# 6_cpu_registers_a.net
KiCad netlist of a schematic drawn in EAGLE
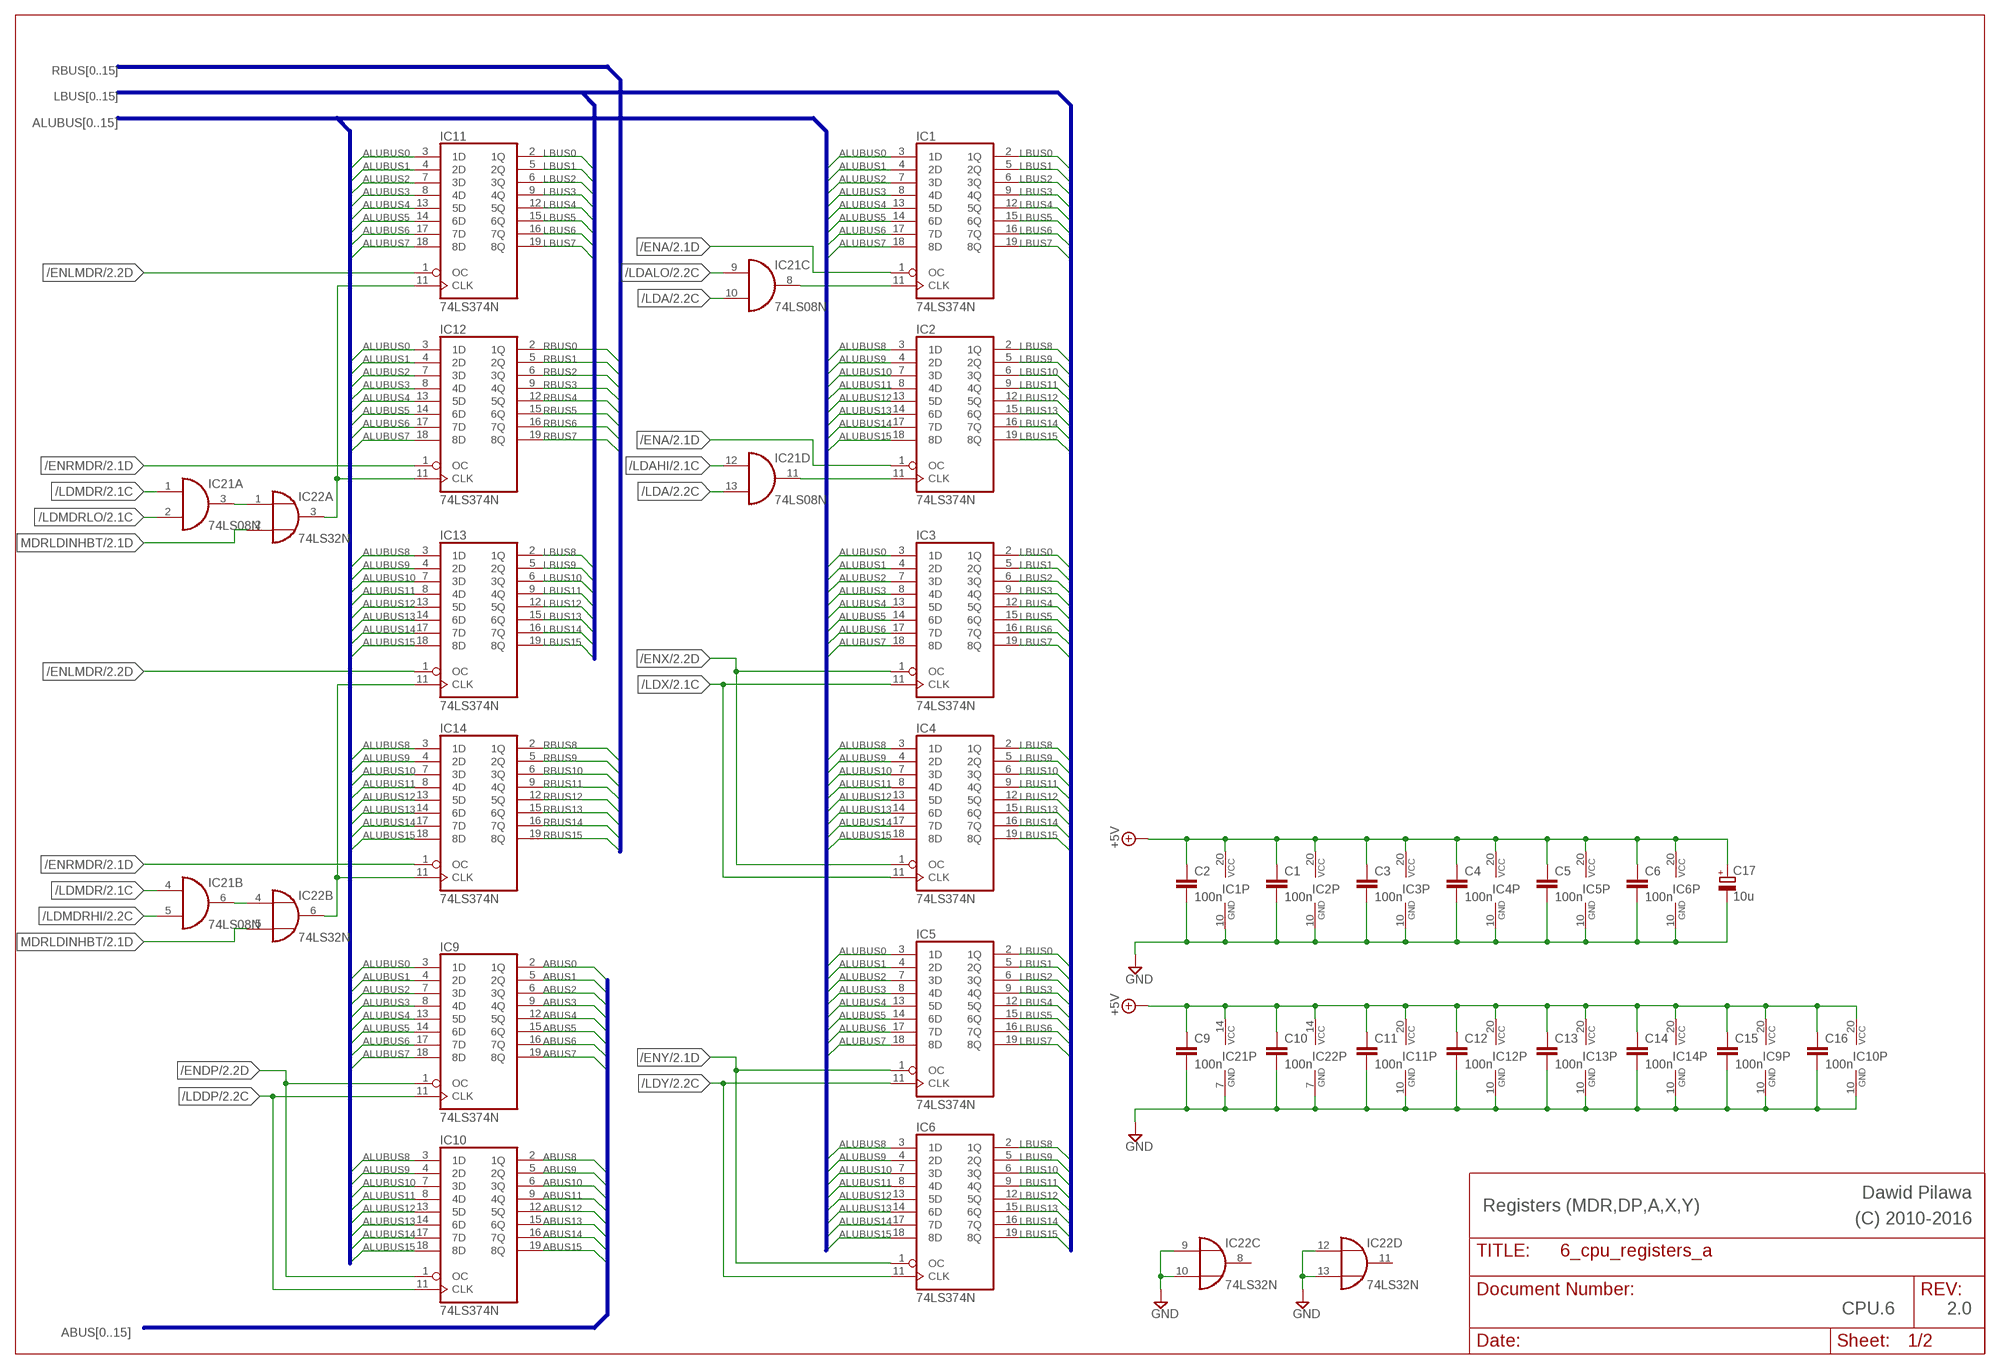
[diagram p0: schematic, sheet 1]
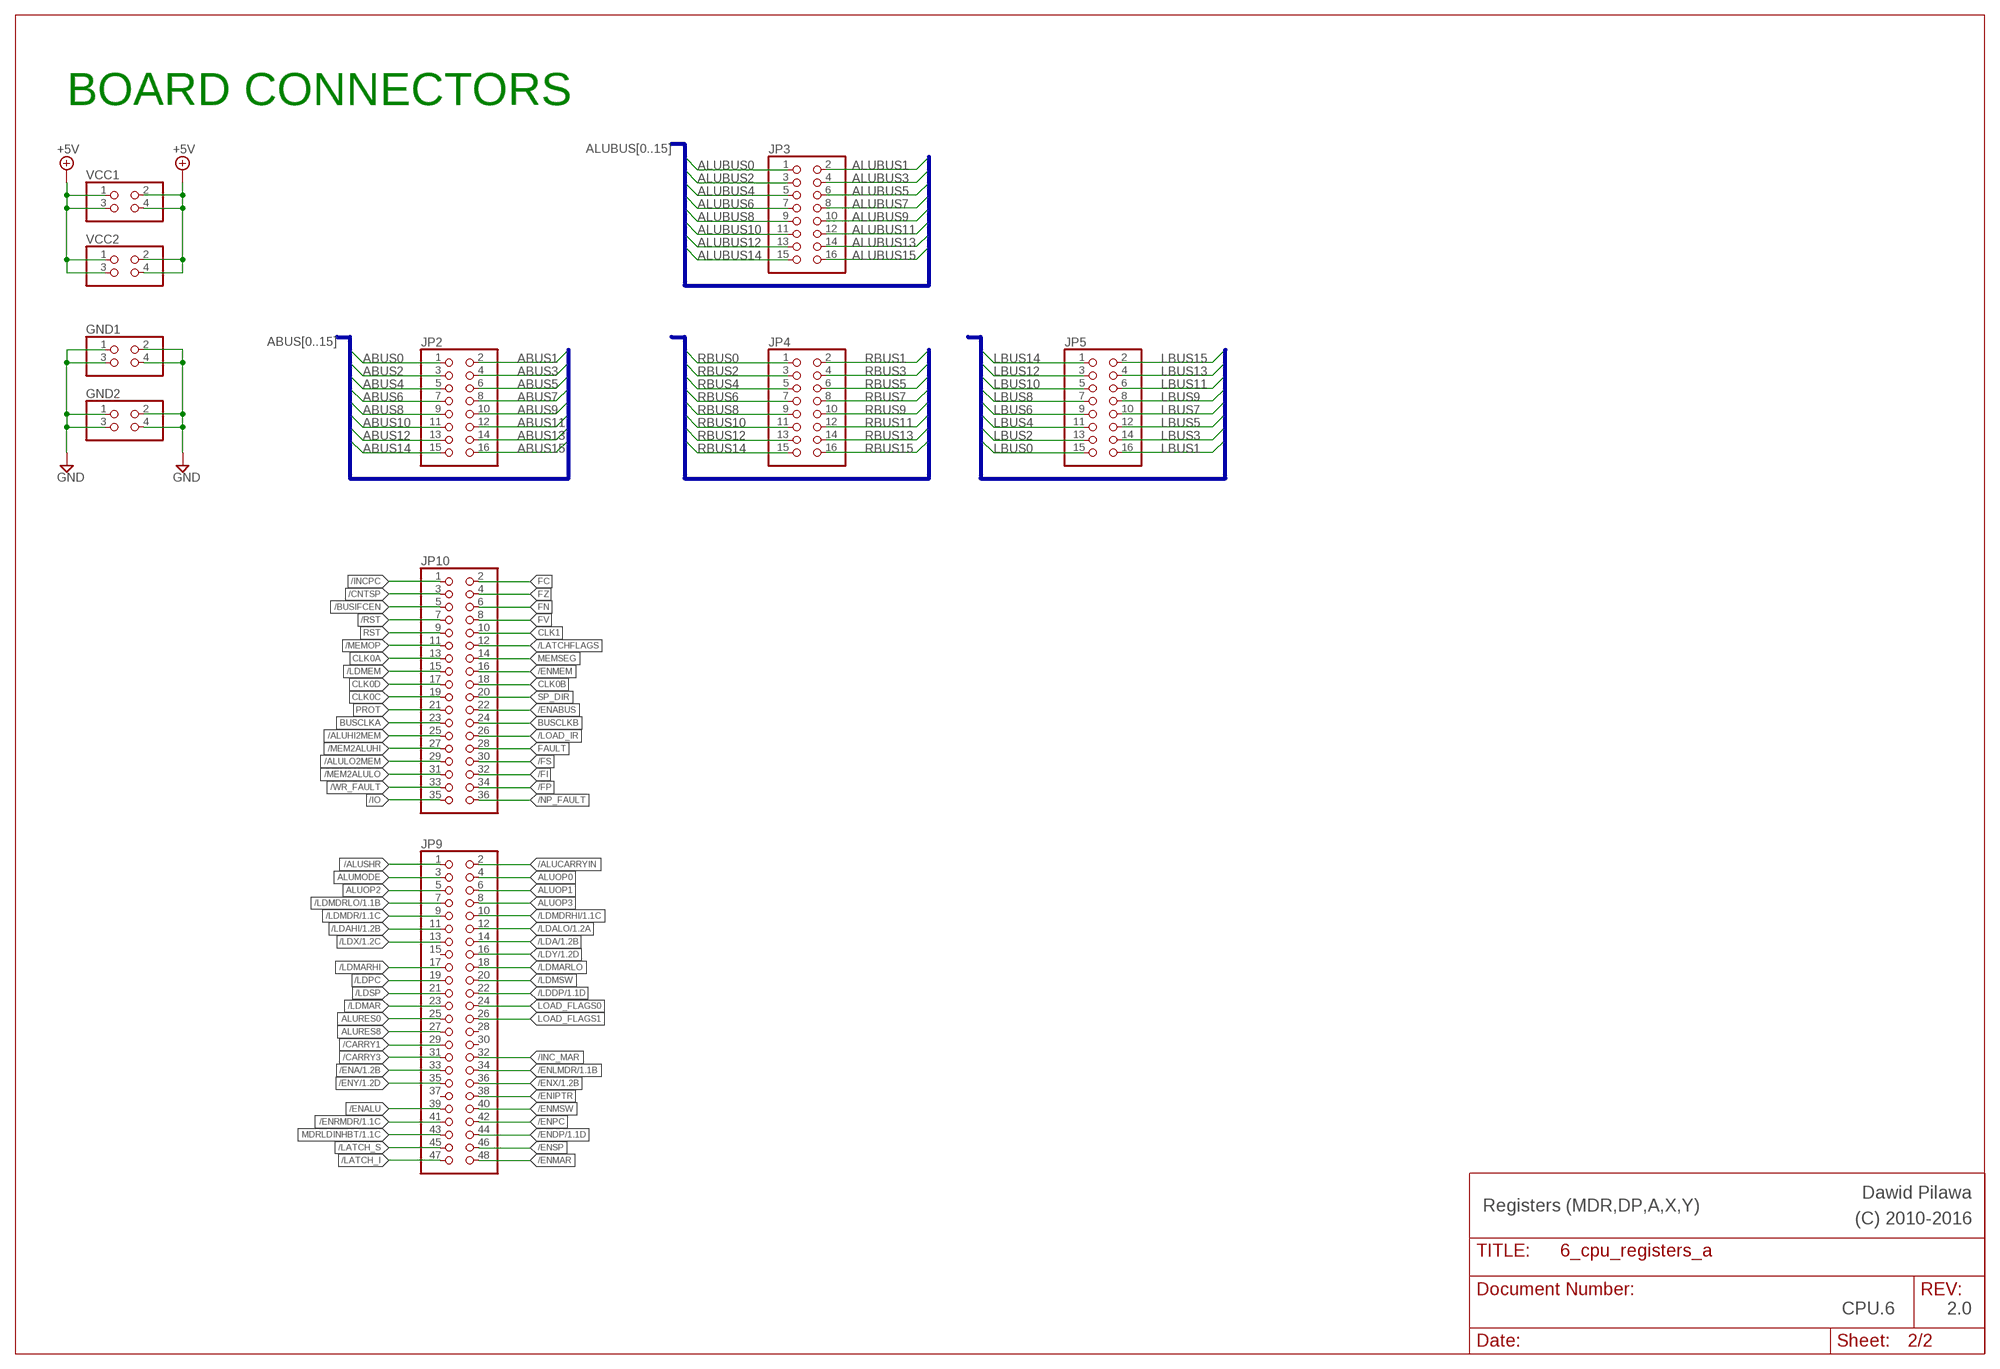
[diagram p1: schematic, sheet 2]

(export (version "E")
  (design (tool "Eeschema 10.0.6"))
  (components
    (comp (ref "C1")
      (value "100n")
      (footprint "eagle-import:C050-024X044")
      (libsource (lib "eagle-import") (part "C-EU050-024X044"))
    )
    (comp (ref "C2")
      (value "100n")
      (footprint "eagle-import:C050-024X044")
      (libsource (lib "eagle-import") (part "C-EU050-024X044"))
    )
    (comp (ref "C3")
      (value "100n")
      (footprint "eagle-import:C050-024X044")
      (libsource (lib "eagle-import") (part "C-EU050-024X044"))
    )
    (comp (ref "C4")
      (value "100n")
      (footprint "eagle-import:C050-024X044")
      (libsource (lib "eagle-import") (part "C-EU050-024X044"))
    )
    (comp (ref "C5")
      (value "100n")
      (footprint "eagle-import:C050-024X044")
      (libsource (lib "eagle-import") (part "C-EU050-024X044"))
    )
    (comp (ref "C6")
      (value "100n")
      (footprint "eagle-import:C050-024X044")
      (libsource (lib "eagle-import") (part "C-EU050-024X044"))
    )
    (comp (ref "C9")
      (value "100n")
      (footprint "eagle-import:C050-024X044")
      (libsource (lib "eagle-import") (part "C-EU050-024X044"))
    )
    (comp (ref "C10")
      (value "100n")
      (footprint "eagle-import:C050-024X044")
      (libsource (lib "eagle-import") (part "C-EU050-024X044"))
    )
    (comp (ref "C11")
      (value "100n")
      (footprint "eagle-import:C050-024X044")
      (libsource (lib "eagle-import") (part "C-EU050-024X044"))
    )
    (comp (ref "C12")
      (value "100n")
      (footprint "eagle-import:C050-024X044")
      (libsource (lib "eagle-import") (part "C-EU050-024X044"))
    )
    (comp (ref "C13")
      (value "100n")
      (footprint "eagle-import:C050-024X044")
      (libsource (lib "eagle-import") (part "C-EU050-024X044"))
    )
    (comp (ref "C14")
      (value "100n")
      (footprint "eagle-import:C050-024X044")
      (libsource (lib "eagle-import") (part "C-EU050-024X044"))
    )
    (comp (ref "C15")
      (value "100n")
      (footprint "eagle-import:C050-024X044")
      (libsource (lib "eagle-import") (part "C-EU050-024X044"))
    )
    (comp (ref "C16")
      (value "100n")
      (footprint "eagle-import:C050-024X044")
      (libsource (lib "eagle-import") (part "C-EU050-024X044"))
    )
    (comp (ref "C17")
      (value "10u")
      (footprint "eagle-import:E2,5-6")
      (libsource (lib "eagle-import") (part "CPOL-EUE2.5-6"))
    )
    (comp (ref "IC1")
      (value "74LS374N")
      (footprint "eagle-import:DIL20")
      (libsource (lib "eagle-import") (part "74374NLS"))
    )
    (comp (ref "IC2")
      (value "74LS374N")
      (footprint "eagle-import:DIL20")
      (libsource (lib "eagle-import") (part "74374NLS"))
    )
    (comp (ref "IC3")
      (value "74LS374N")
      (footprint "eagle-import:DIL20")
      (libsource (lib "eagle-import") (part "74374NLS"))
    )
    (comp (ref "IC4")
      (value "74LS374N")
      (footprint "eagle-import:DIL20")
      (libsource (lib "eagle-import") (part "74374NLS"))
    )
    (comp (ref "IC5")
      (value "74LS374N")
      (footprint "eagle-import:DIL20")
      (libsource (lib "eagle-import") (part "74374NLS"))
    )
    (comp (ref "IC6")
      (value "74LS374N")
      (footprint "eagle-import:DIL20")
      (libsource (lib "eagle-import") (part "74374NLS"))
    )
    (comp (ref "IC9")
      (value "74LS374N")
      (footprint "eagle-import:DIL20")
      (libsource (lib "eagle-import") (part "74374NLS"))
    )
    (comp (ref "IC10")
      (value "74LS374N")
      (footprint "eagle-import:DIL20")
      (libsource (lib "eagle-import") (part "74374NLS"))
    )
    (comp (ref "IC11")
      (value "74LS374N")
      (footprint "eagle-import:DIL20")
      (libsource (lib "eagle-import") (part "74374NLS"))
    )
    (comp (ref "IC12")
      (value "74LS374N")
      (footprint "eagle-import:DIL20")
      (libsource (lib "eagle-import") (part "74374NLS"))
    )
    (comp (ref "IC13")
      (value "74LS374N")
      (footprint "eagle-import:DIL20")
      (libsource (lib "eagle-import") (part "74374NLS"))
    )
    (comp (ref "IC14")
      (value "74LS374N")
      (footprint "eagle-import:DIL20")
      (libsource (lib "eagle-import") (part "74374NLS"))
    )
    (comp (ref "IC21")
      (value "74LS08N")
      (footprint "eagle-import:DIL14")
      (libsource (lib "eagle-import") (part "7408NLS"))
    )
    (comp (ref "IC22")
      (value "74LS32N")
      (footprint "eagle-import:DIL14")
      (libsource (lib "eagle-import") (part "7432NLS"))
    )
    (comp (ref "GND1")
      (value "PINHD-2X2")
      (footprint "eagle-import:2X02")
      (libsource (lib "eagle-import") (part "PINHD-2X2"))
    )
    (comp (ref "GND2")
      (value "PINHD-2X2")
      (footprint "eagle-import:2X02")
      (libsource (lib "eagle-import") (part "PINHD-2X2"))
    )
    (comp (ref "JP2")
      (value "PINHD-2X8")
      (footprint "eagle-import:2X08")
      (libsource (lib "eagle-import") (part "PINHD-2X8"))
    )
    (comp (ref "JP3")
      (value "PINHD-2X8")
      (footprint "eagle-import:2X08")
      (libsource (lib "eagle-import") (part "PINHD-2X8"))
    )
    (comp (ref "JP4")
      (value "PINHD-2X8")
      (footprint "eagle-import:2X08")
      (libsource (lib "eagle-import") (part "PINHD-2X8"))
    )
    (comp (ref "JP5")
      (value "PINHD-2X8")
      (footprint "eagle-import:2X08")
      (libsource (lib "eagle-import") (part "PINHD-2X8"))
    )
    (comp (ref "JP9")
      (value "PINHD-2X24")
      (footprint "eagle-import:2X24")
      (libsource (lib "eagle-import") (part "PINHD-2X24"))
    )
    (comp (ref "JP10")
      (value "PINHD-2X18")
      (footprint "eagle-import:2X18")
      (libsource (lib "eagle-import") (part "PINHD-2X18"))
    )
    (comp (ref "VCC1")
      (value "PINHD-2X2")
      (footprint "eagle-import:2X02")
      (libsource (lib "eagle-import") (part "PINHD-2X2"))
    )
    (comp (ref "VCC2")
      (value "PINHD-2X2")
      (footprint "eagle-import:2X02")
      (libsource (lib "eagle-import") (part "PINHD-2X2"))
    )
  )
  (nets
    (net (code "1") (name "+5V") (class "Default")
      (node (ref "C1") (pin "1") (pinfunction "1_1") (pintype "passive"))
      (node (ref "C10") (pin "1") (pinfunction "1_1") (pintype "passive"))
      (node (ref "C11") (pin "1") (pinfunction "1_1") (pintype "passive"))
      (node (ref "C12") (pin "1") (pinfunction "1_1") (pintype "passive"))
      (node (ref "C13") (pin "1") (pinfunction "1_1") (pintype "passive"))
      (node (ref "C14") (pin "1") (pinfunction "1_1") (pintype "passive"))
      (node (ref "C15") (pin "1") (pinfunction "1_1") (pintype "passive"))
      (node (ref "C16") (pin "1") (pinfunction "1_1") (pintype "passive"))
      (node (ref "C17") (pin "+") (pinfunction "+_+") (pintype "passive"))
      (node (ref "C2") (pin "1") (pinfunction "1_1") (pintype "passive"))
      (node (ref "C3") (pin "1") (pinfunction "1_1") (pintype "passive"))
      (node (ref "C4") (pin "1") (pinfunction "1_1") (pintype "passive"))
      (node (ref "C5") (pin "1") (pinfunction "1_1") (pintype "passive"))
      (node (ref "C6") (pin "1") (pinfunction "1_1") (pintype "passive"))
      (node (ref "C9") (pin "1") (pinfunction "1_1") (pintype "passive"))
      (node (ref "IC1") (pin "20") (pinfunction "VCC_20") (pintype "power_in"))
      (node (ref "IC10") (pin "20") (pinfunction "VCC_20") (pintype "power_in"))
      (node (ref "IC11") (pin "20") (pinfunction "VCC_20") (pintype "power_in"))
      (node (ref "IC12") (pin "20") (pinfunction "VCC_20") (pintype "power_in"))
      (node (ref "IC13") (pin "20") (pinfunction "VCC_20") (pintype "power_in"))
      (node (ref "IC14") (pin "20") (pinfunction "VCC_20") (pintype "power_in"))
      (node (ref "IC2") (pin "20") (pinfunction "VCC_20") (pintype "power_in"))
      (node (ref "IC21") (pin "14") (pinfunction "VCC_14") (pintype "power_in"))
      (node (ref "IC22") (pin "14") (pinfunction "VCC_14") (pintype "power_in"))
      (node (ref "IC3") (pin "20") (pinfunction "VCC_20") (pintype "power_in"))
      (node (ref "IC4") (pin "20") (pinfunction "VCC_20") (pintype "power_in"))
      (node (ref "IC5") (pin "20") (pinfunction "VCC_20") (pintype "power_in"))
      (node (ref "IC6") (pin "20") (pinfunction "VCC_20") (pintype "power_in"))
      (node (ref "IC9") (pin "20") (pinfunction "VCC_20") (pintype "power_in"))
      (node (ref "VCC1") (pin "1") (pinfunction "1_1") (pintype "passive"))
      (node (ref "VCC1") (pin "2") (pinfunction "2_2") (pintype "passive"))
      (node (ref "VCC1") (pin "3") (pinfunction "3_3") (pintype "passive"))
      (node (ref "VCC1") (pin "4") (pinfunction "4_4") (pintype "passive"))
      (node (ref "VCC2") (pin "1") (pinfunction "1_1") (pintype "passive"))
      (node (ref "VCC2") (pin "2") (pinfunction "2_2") (pintype "passive"))
      (node (ref "VCC2") (pin "3") (pinfunction "3_3") (pintype "passive"))
      (node (ref "VCC2") (pin "4") (pinfunction "4_4") (pintype "passive"))
    )
    (net (code "8") (name "ABUS0") (class "Default")
      (node (ref "IC9") (pin "2") (pinfunction "1Q_2") (pintype "tri_state"))
      (node (ref "JP2") (pin "1") (pinfunction "1_1") (pintype "passive"))
    )
    (net (code "9") (name "ABUS1") (class "Default")
      (node (ref "IC9") (pin "5") (pinfunction "2Q_5") (pintype "tri_state"))
      (node (ref "JP2") (pin "2") (pinfunction "2_2") (pintype "passive"))
    )
    (net (code "10") (name "ABUS2") (class "Default")
      (node (ref "IC9") (pin "6") (pinfunction "3Q_6") (pintype "tri_state"))
      (node (ref "JP2") (pin "3") (pinfunction "3_3") (pintype "passive"))
    )
    (net (code "11") (name "ABUS3") (class "Default")
      (node (ref "IC9") (pin "9") (pinfunction "4Q_9") (pintype "tri_state"))
      (node (ref "JP2") (pin "4") (pinfunction "4_4") (pintype "passive"))
    )
    (net (code "12") (name "ABUS4") (class "Default")
      (node (ref "IC9") (pin "12") (pinfunction "5Q_12") (pintype "tri_state"))
      (node (ref "JP2") (pin "5") (pinfunction "5_5") (pintype "passive"))
    )
    (net (code "13") (name "ABUS5") (class "Default")
      (node (ref "IC9") (pin "15") (pinfunction "6Q_15") (pintype "tri_state"))
      (node (ref "JP2") (pin "6") (pinfunction "6_6") (pintype "passive"))
    )
    (net (code "14") (name "ABUS6") (class "Default")
      (node (ref "IC9") (pin "16") (pinfunction "7Q_16") (pintype "tri_state"))
      (node (ref "JP2") (pin "7") (pinfunction "7_7") (pintype "passive"))
    )
    (net (code "15") (name "ABUS7") (class "Default")
      (node (ref "IC9") (pin "19") (pinfunction "8Q_19") (pintype "tri_state"))
      (node (ref "JP2") (pin "8") (pinfunction "8_8") (pintype "passive"))
    )
    (net (code "16") (name "ABUS8") (class "Default")
      (node (ref "IC10") (pin "2") (pinfunction "1Q_2") (pintype "tri_state"))
      (node (ref "JP2") (pin "9") (pinfunction "9_9") (pintype "passive"))
    )
    (net (code "17") (name "ABUS9") (class "Default")
      (node (ref "IC10") (pin "5") (pinfunction "2Q_5") (pintype "tri_state"))
      (node (ref "JP2") (pin "10") (pinfunction "10_10") (pintype "passive"))
    )
    (net (code "18") (name "ABUS10") (class "Default")
      (node (ref "IC10") (pin "6") (pinfunction "3Q_6") (pintype "tri_state"))
      (node (ref "JP2") (pin "11") (pinfunction "11_11") (pintype "passive"))
    )
    (net (code "19") (name "ABUS11") (class "Default")
      (node (ref "IC10") (pin "9") (pinfunction "4Q_9") (pintype "tri_state"))
      (node (ref "JP2") (pin "12") (pinfunction "12_12") (pintype "passive"))
    )
    (net (code "20") (name "ABUS12") (class "Default")
      (node (ref "IC10") (pin "12") (pinfunction "5Q_12") (pintype "tri_state"))
      (node (ref "JP2") (pin "13") (pinfunction "13_13") (pintype "passive"))
    )
    (net (code "21") (name "ABUS13") (class "Default")
      (node (ref "IC10") (pin "15") (pinfunction "6Q_15") (pintype "tri_state"))
      (node (ref "JP2") (pin "14") (pinfunction "14_14") (pintype "passive"))
    )
    (net (code "22") (name "ABUS14") (class "Default")
      (node (ref "IC10") (pin "16") (pinfunction "7Q_16") (pintype "tri_state"))
      (node (ref "JP2") (pin "15") (pinfunction "15_15") (pintype "passive"))
    )
    (net (code "23") (name "ABUS15") (class "Default")
      (node (ref "IC10") (pin "19") (pinfunction "8Q_19") (pintype "tri_state"))
      (node (ref "JP2") (pin "16") (pinfunction "16_16") (pintype "passive"))
    )
    (net (code "24") (name "ALUBUS0") (class "Default")
      (node (ref "IC1") (pin "3") (pinfunction "1D_3") (pintype "input"))
      (node (ref "IC11") (pin "3") (pinfunction "1D_3") (pintype "input"))
      (node (ref "IC12") (pin "3") (pinfunction "1D_3") (pintype "input"))
      (node (ref "IC3") (pin "3") (pinfunction "1D_3") (pintype "input"))
      (node (ref "IC5") (pin "3") (pinfunction "1D_3") (pintype "input"))
      (node (ref "IC9") (pin "3") (pinfunction "1D_3") (pintype "input"))
      (node (ref "JP3") (pin "1") (pinfunction "1_1") (pintype "passive"))
    )
    (net (code "25") (name "ALUBUS1") (class "Default")
      (node (ref "IC1") (pin "4") (pinfunction "2D_4") (pintype "input"))
      (node (ref "IC11") (pin "4") (pinfunction "2D_4") (pintype "input"))
      (node (ref "IC12") (pin "4") (pinfunction "2D_4") (pintype "input"))
      (node (ref "IC3") (pin "4") (pinfunction "2D_4") (pintype "input"))
      (node (ref "IC5") (pin "4") (pinfunction "2D_4") (pintype "input"))
      (node (ref "IC9") (pin "4") (pinfunction "2D_4") (pintype "input"))
      (node (ref "JP3") (pin "2") (pinfunction "2_2") (pintype "passive"))
    )
    (net (code "26") (name "ALUBUS2") (class "Default")
      (node (ref "IC1") (pin "7") (pinfunction "3D_7") (pintype "input"))
      (node (ref "IC11") (pin "7") (pinfunction "3D_7") (pintype "input"))
      (node (ref "IC12") (pin "7") (pinfunction "3D_7") (pintype "input"))
      (node (ref "IC3") (pin "7") (pinfunction "3D_7") (pintype "input"))
      (node (ref "IC5") (pin "7") (pinfunction "3D_7") (pintype "input"))
      (node (ref "IC9") (pin "7") (pinfunction "3D_7") (pintype "input"))
      (node (ref "JP3") (pin "3") (pinfunction "3_3") (pintype "passive"))
    )
    (net (code "27") (name "ALUBUS3") (class "Default")
      (node (ref "IC1") (pin "8") (pinfunction "4D_8") (pintype "input"))
      (node (ref "IC11") (pin "8") (pinfunction "4D_8") (pintype "input"))
      (node (ref "IC12") (pin "8") (pinfunction "4D_8") (pintype "input"))
      (node (ref "IC3") (pin "8") (pinfunction "4D_8") (pintype "input"))
      (node (ref "IC5") (pin "8") (pinfunction "4D_8") (pintype "input"))
      (node (ref "IC9") (pin "8") (pinfunction "4D_8") (pintype "input"))
      (node (ref "JP3") (pin "4") (pinfunction "4_4") (pintype "passive"))
    )
    (net (code "28") (name "ALUBUS4") (class "Default")
      (node (ref "IC1") (pin "13") (pinfunction "5D_13") (pintype "input"))
      (node (ref "IC11") (pin "13") (pinfunction "5D_13") (pintype "input"))
      (node (ref "IC12") (pin "13") (pinfunction "5D_13") (pintype "input"))
      (node (ref "IC3") (pin "13") (pinfunction "5D_13") (pintype "input"))
      (node (ref "IC5") (pin "13") (pinfunction "5D_13") (pintype "input"))
      (node (ref "IC9") (pin "13") (pinfunction "5D_13") (pintype "input"))
      (node (ref "JP3") (pin "5") (pinfunction "5_5") (pintype "passive"))
    )
    (net (code "29") (name "ALUBUS5") (class "Default")
      (node (ref "IC1") (pin "14") (pinfunction "6D_14") (pintype "input"))
      (node (ref "IC11") (pin "14") (pinfunction "6D_14") (pintype "input"))
      (node (ref "IC12") (pin "14") (pinfunction "6D_14") (pintype "input"))
      (node (ref "IC3") (pin "14") (pinfunction "6D_14") (pintype "input"))
      (node (ref "IC5") (pin "14") (pinfunction "6D_14") (pintype "input"))
      (node (ref "IC9") (pin "14") (pinfunction "6D_14") (pintype "input"))
      (node (ref "JP3") (pin "6") (pinfunction "6_6") (pintype "passive"))
    )
    (net (code "30") (name "ALUBUS6") (class "Default")
      (node (ref "IC1") (pin "17") (pinfunction "7D_17") (pintype "input"))
      (node (ref "IC11") (pin "17") (pinfunction "7D_17") (pintype "input"))
      (node (ref "IC12") (pin "17") (pinfunction "7D_17") (pintype "input"))
      (node (ref "IC3") (pin "17") (pinfunction "7D_17") (pintype "input"))
      (node (ref "IC5") (pin "17") (pinfunction "7D_17") (pintype "input"))
      (node (ref "IC9") (pin "17") (pinfunction "7D_17") (pintype "input"))
      (node (ref "JP3") (pin "7") (pinfunction "7_7") (pintype "passive"))
    )
    (net (code "31") (name "ALUBUS7") (class "Default")
      (node (ref "IC1") (pin "18") (pinfunction "8D_18") (pintype "input"))
      (node (ref "IC11") (pin "18") (pinfunction "8D_18") (pintype "input"))
      (node (ref "IC12") (pin "18") (pinfunction "8D_18") (pintype "input"))
      (node (ref "IC3") (pin "18") (pinfunction "8D_18") (pintype "input"))
      (node (ref "IC5") (pin "18") (pinfunction "8D_18") (pintype "input"))
      (node (ref "IC9") (pin "18") (pinfunction "8D_18") (pintype "input"))
      (node (ref "JP3") (pin "8") (pinfunction "8_8") (pintype "passive"))
    )
    (net (code "32") (name "ALUBUS8") (class "Default")
      (node (ref "IC10") (pin "3") (pinfunction "1D_3") (pintype "input"))
      (node (ref "IC13") (pin "3") (pinfunction "1D_3") (pintype "input"))
      (node (ref "IC14") (pin "3") (pinfunction "1D_3") (pintype "input"))
      (node (ref "IC2") (pin "3") (pinfunction "1D_3") (pintype "input"))
      (node (ref "IC4") (pin "3") (pinfunction "1D_3") (pintype "input"))
      (node (ref "IC6") (pin "3") (pinfunction "1D_3") (pintype "input"))
      (node (ref "JP3") (pin "9") (pinfunction "9_9") (pintype "passive"))
    )
    (net (code "33") (name "ALUBUS9") (class "Default")
      (node (ref "IC10") (pin "4") (pinfunction "2D_4") (pintype "input"))
      (node (ref "IC13") (pin "4") (pinfunction "2D_4") (pintype "input"))
      (node (ref "IC14") (pin "4") (pinfunction "2D_4") (pintype "input"))
      (node (ref "IC2") (pin "4") (pinfunction "2D_4") (pintype "input"))
      (node (ref "IC4") (pin "4") (pinfunction "2D_4") (pintype "input"))
      (node (ref "IC6") (pin "4") (pinfunction "2D_4") (pintype "input"))
      (node (ref "JP3") (pin "10") (pinfunction "10_10") (pintype "passive"))
    )
    (net (code "34") (name "ALUBUS10") (class "Default")
      (node (ref "IC10") (pin "7") (pinfunction "3D_7") (pintype "input"))
      (node (ref "IC13") (pin "7") (pinfunction "3D_7") (pintype "input"))
      (node (ref "IC14") (pin "7") (pinfunction "3D_7") (pintype "input"))
      (node (ref "IC2") (pin "7") (pinfunction "3D_7") (pintype "input"))
      (node (ref "IC4") (pin "7") (pinfunction "3D_7") (pintype "input"))
      (node (ref "IC6") (pin "7") (pinfunction "3D_7") (pintype "input"))
      (node (ref "JP3") (pin "11") (pinfunction "11_11") (pintype "passive"))
    )
    (net (code "35") (name "ALUBUS11") (class "Default")
      (node (ref "IC10") (pin "8") (pinfunction "4D_8") (pintype "input"))
      (node (ref "IC13") (pin "8") (pinfunction "4D_8") (pintype "input"))
      (node (ref "IC14") (pin "8") (pinfunction "4D_8") (pintype "input"))
      (node (ref "IC2") (pin "8") (pinfunction "4D_8") (pintype "input"))
      (node (ref "IC4") (pin "8") (pinfunction "4D_8") (pintype "input"))
      (node (ref "IC6") (pin "8") (pinfunction "4D_8") (pintype "input"))
      (node (ref "JP3") (pin "12") (pinfunction "12_12") (pintype "passive"))
    )
    (net (code "36") (name "ALUBUS12") (class "Default")
      (node (ref "IC10") (pin "13") (pinfunction "5D_13") (pintype "input"))
      (node (ref "IC13") (pin "13") (pinfunction "5D_13") (pintype "input"))
      (node (ref "IC14") (pin "13") (pinfunction "5D_13") (pintype "input"))
      (node (ref "IC2") (pin "13") (pinfunction "5D_13") (pintype "input"))
      (node (ref "IC4") (pin "13") (pinfunction "5D_13") (pintype "input"))
      (node (ref "IC6") (pin "13") (pinfunction "5D_13") (pintype "input"))
      (node (ref "JP3") (pin "13") (pinfunction "13_13") (pintype "passive"))
    )
    (net (code "37") (name "ALUBUS13") (class "Default")
      (node (ref "IC10") (pin "14") (pinfunction "6D_14") (pintype "input"))
      (node (ref "IC13") (pin "14") (pinfunction "6D_14") (pintype "input"))
      (node (ref "IC14") (pin "14") (pinfunction "6D_14") (pintype "input"))
      (node (ref "IC2") (pin "14") (pinfunction "6D_14") (pintype "input"))
      (node (ref "IC4") (pin "14") (pinfunction "6D_14") (pintype "input"))
      (node (ref "IC6") (pin "14") (pinfunction "6D_14") (pintype "input"))
      (node (ref "JP3") (pin "14") (pinfunction "14_14") (pintype "passive"))
    )
    (net (code "38") (name "ALUBUS14") (class "Default")
      (node (ref "IC10") (pin "17") (pinfunction "7D_17") (pintype "input"))
      (node (ref "IC13") (pin "17") (pinfunction "7D_17") (pintype "input"))
      (node (ref "IC14") (pin "17") (pinfunction "7D_17") (pintype "input"))
      (node (ref "IC2") (pin "17") (pinfunction "7D_17") (pintype "input"))
      (node (ref "IC4") (pin "17") (pinfunction "7D_17") (pintype "input"))
      (node (ref "IC6") (pin "17") (pinfunction "7D_17") (pintype "input"))
      (node (ref "JP3") (pin "15") (pinfunction "15_15") (pintype "passive"))
    )
    (net (code "39") (name "ALUBUS15") (class "Default")
      (node (ref "IC10") (pin "18") (pinfunction "8D_18") (pintype "input"))
      (node (ref "IC13") (pin "18") (pinfunction "8D_18") (pintype "input"))
      (node (ref "IC14") (pin "18") (pinfunction "8D_18") (pintype "input"))
      (node (ref "IC2") (pin "18") (pinfunction "8D_18") (pintype "input"))
      (node (ref "IC4") (pin "18") (pinfunction "8D_18") (pintype "input"))
      (node (ref "IC6") (pin "18") (pinfunction "8D_18") (pintype "input"))
      (node (ref "JP3") (pin "16") (pinfunction "16_16") (pintype "passive"))
    )
    (net (code "40") (name "ALUMODE") (class "Default")
      (node (ref "JP9") (pin "3") (pinfunction "3_3") (pintype "passive"))
    )
    (net (code "41") (name "ALUOP0") (class "Default")
      (node (ref "JP9") (pin "4") (pinfunction "4_4") (pintype "passive"))
    )
    (net (code "42") (name "ALUOP1") (class "Default")
      (node (ref "JP9") (pin "6") (pinfunction "6_6") (pintype "passive"))
    )
    (net (code "43") (name "ALUOP2") (class "Default")
      (node (ref "JP9") (pin "5") (pinfunction "5_5") (pintype "passive"))
    )
    (net (code "44") (name "ALUOP3") (class "Default")
      (node (ref "JP9") (pin "8") (pinfunction "8_8") (pintype "passive"))
    )
    (net (code "45") (name "ALURES0") (class "Default")
      (node (ref "JP9") (pin "25") (pinfunction "25_25") (pintype "passive"))
    )
    (net (code "46") (name "ALURES8") (class "Default")
      (node (ref "JP9") (pin "27") (pinfunction "27_27") (pintype "passive"))
    )
    (net (code "47") (name "BUSCLKA") (class "Default")
      (node (ref "JP10") (pin "23") (pinfunction "23_23") (pintype "passive"))
    )
    (net (code "48") (name "BUSCLKB") (class "Default")
      (node (ref "JP10") (pin "24") (pinfunction "24_24") (pintype "passive"))
    )
    (net (code "49") (name "CLK0A") (class "Default")
      (node (ref "JP10") (pin "13") (pinfunction "13_13") (pintype "passive"))
    )
    (net (code "50") (name "CLK0B") (class "Default")
      (node (ref "JP10") (pin "18") (pinfunction "18_18") (pintype "passive"))
    )
    (net (code "51") (name "CLK0C") (class "Default")
      (node (ref "JP10") (pin "19") (pinfunction "19_19") (pintype "passive"))
    )
    (net (code "52") (name "CLK0D") (class "Default")
      (node (ref "JP10") (pin "17") (pinfunction "17_17") (pintype "passive"))
    )
    (net (code "53") (name "CLK1") (class "Default")
      (node (ref "JP10") (pin "10") (pinfunction "10_10") (pintype "passive"))
    )
    (net (code "54") (name "FAULT") (class "Default")
      (node (ref "JP10") (pin "28") (pinfunction "28_28") (pintype "passive"))
    )
    (net (code "55") (name "FC") (class "Default")
      (node (ref "JP10") (pin "2") (pinfunction "2_2") (pintype "passive"))
    )
    (net (code "56") (name "FN") (class "Default")
      (node (ref "JP10") (pin "6") (pinfunction "6_6") (pintype "passive"))
    )
    (net (code "57") (name "FV") (class "Default")
      (node (ref "JP10") (pin "8") (pinfunction "8_8") (pintype "passive"))
    )
    (net (code "58") (name "FZ") (class "Default")
      (node (ref "JP10") (pin "4") (pinfunction "4_4") (pintype "passive"))
    )
    (net (code "59") (name "GND") (class "Default")
      (node (ref "C1") (pin "2") (pinfunction "2_2") (pintype "passive"))
      (node (ref "C10") (pin "2") (pinfunction "2_2") (pintype "passive"))
      (node (ref "C11") (pin "2") (pinfunction "2_2") (pintype "passive"))
      (node (ref "C12") (pin "2") (pinfunction "2_2") (pintype "passive"))
      (node (ref "C13") (pin "2") (pinfunction "2_2") (pintype "passive"))
      (node (ref "C14") (pin "2") (pinfunction "2_2") (pintype "passive"))
      (node (ref "C15") (pin "2") (pinfunction "2_2") (pintype "passive"))
      (node (ref "C16") (pin "2") (pinfunction "2_2") (pintype "passive"))
      (node (ref "C17") (pin "-") (pinfunction "-_-") (pintype "passive"))
      (node (ref "C2") (pin "2") (pinfunction "2_2") (pintype "passive"))
      (node (ref "C3") (pin "2") (pinfunction "2_2") (pintype "passive"))
      (node (ref "C4") (pin "2") (pinfunction "2_2") (pintype "passive"))
      (node (ref "C5") (pin "2") (pinfunction "2_2") (pintype "passive"))
      (node (ref "C6") (pin "2") (pinfunction "2_2") (pintype "passive"))
      (node (ref "C9") (pin "2") (pinfunction "2_2") (pintype "passive"))
      (node (ref "GND1") (pin "1") (pinfunction "1_1") (pintype "passive"))
      (node (ref "GND1") (pin "2") (pinfunction "2_2") (pintype "passive"))
      (node (ref "GND1") (pin "3") (pinfunction "3_3") (pintype "passive"))
      (node (ref "GND1") (pin "4") (pinfunction "4_4") (pintype "passive"))
      (node (ref "GND2") (pin "1") (pinfunction "1_1") (pintype "passive"))
      (node (ref "GND2") (pin "2") (pinfunction "2_2") (pintype "passive"))
      (node (ref "GND2") (pin "3") (pinfunction "3_3") (pintype "passive"))
      (node (ref "GND2") (pin "4") (pinfunction "4_4") (pintype "passive"))
      (node (ref "IC1") (pin "10") (pinfunction "GND_10") (pintype "power_in"))
      (node (ref "IC10") (pin "10") (pinfunction "GND_10") (pintype "power_in"))
      (node (ref "IC11") (pin "10") (pinfunction "GND_10") (pintype "power_in"))
      (node (ref "IC12") (pin "10") (pinfunction "GND_10") (pintype "power_in"))
      (node (ref "IC13") (pin "10") (pinfunction "GND_10") (pintype "power_in"))
      (node (ref "IC14") (pin "10") (pinfunction "GND_10") (pintype "power_in"))
      (node (ref "IC2") (pin "10") (pinfunction "GND_10") (pintype "power_in"))
      (node (ref "IC21") (pin "7") (pinfunction "GND_7") (pintype "power_in"))
      (node (ref "IC22") (pin "10") (pinfunction "I1_10") (pintype "input"))
      (node (ref "IC22") (pin "12") (pinfunction "I0_12") (pintype "input"))
      (node (ref "IC22") (pin "13") (pinfunction "I1_13") (pintype "input"))
      (node (ref "IC22") (pin "7") (pinfunction "GND_7") (pintype "power_in"))
      (node (ref "IC22") (pin "9") (pinfunction "I0_9") (pintype "input"))
      (node (ref "IC3") (pin "10") (pinfunction "GND_10") (pintype "power_in"))
      (node (ref "IC4") (pin "10") (pinfunction "GND_10") (pintype "power_in"))
      (node (ref "IC5") (pin "10") (pinfunction "GND_10") (pintype "power_in"))
      (node (ref "IC6") (pin "10") (pinfunction "GND_10") (pintype "power_in"))
      (node (ref "IC9") (pin "10") (pinfunction "GND_10") (pintype "power_in"))
    )
    (net (code "60") (name "LBUS0") (class "Default")
      (node (ref "IC1") (pin "2") (pinfunction "1Q_2") (pintype "tri_state"))
      (node (ref "IC11") (pin "2") (pinfunction "1Q_2") (pintype "tri_state"))
      (node (ref "IC3") (pin "2") (pinfunction "1Q_2") (pintype "tri_state"))
      (node (ref "IC5") (pin "2") (pinfunction "1Q_2") (pintype "tri_state"))
      (node (ref "JP5") (pin "15") (pinfunction "15_15") (pintype "passive"))
    )
    (net (code "61") (name "LBUS1") (class "Default")
      (node (ref "IC1") (pin "5") (pinfunction "2Q_5") (pintype "tri_state"))
      (node (ref "IC11") (pin "5") (pinfunction "2Q_5") (pintype "tri_state"))
      (node (ref "IC3") (pin "5") (pinfunction "2Q_5") (pintype "tri_state"))
      (node (ref "IC5") (pin "5") (pinfunction "2Q_5") (pintype "tri_state"))
      (node (ref "JP5") (pin "16") (pinfunction "16_16") (pintype "passive"))
    )
    (net (code "62") (name "LBUS2") (class "Default")
      (node (ref "IC1") (pin "6") (pinfunction "3Q_6") (pintype "tri_state"))
      (node (ref "IC11") (pin "6") (pinfunction "3Q_6") (pintype "tri_state"))
      (node (ref "IC3") (pin "6") (pinfunction "3Q_6") (pintype "tri_state"))
      (node (ref "IC5") (pin "6") (pinfunction "3Q_6") (pintype "tri_state"))
      (node (ref "JP5") (pin "13") (pinfunction "13_13") (pintype "passive"))
    )
    (net (code "63") (name "LBUS3") (class "Default")
      (node (ref "IC1") (pin "9") (pinfunction "4Q_9") (pintype "tri_state"))
      (node (ref "IC11") (pin "9") (pinfunction "4Q_9") (pintype "tri_state"))
      (node (ref "IC3") (pin "9") (pinfunction "4Q_9") (pintype "tri_state"))
      (node (ref "IC5") (pin "9") (pinfunction "4Q_9") (pintype "tri_state"))
      (node (ref "JP5") (pin "14") (pinfunction "14_14") (pintype "passive"))
    )
    (net (code "64") (name "LBUS4") (class "Default")
      (node (ref "IC1") (pin "12") (pinfunction "5Q_12") (pintype "tri_state"))
      (node (ref "IC11") (pin "12") (pinfunction "5Q_12") (pintype "tri_state"))
      (node (ref "IC3") (pin "12") (pinfunction "5Q_12") (pintype "tri_state"))
      (node (ref "IC5") (pin "12") (pinfunction "5Q_12") (pintype "tri_state"))
      (node (ref "JP5") (pin "11") (pinfunction "11_11") (pintype "passive"))
    )
    (net (code "65") (name "LBUS5") (class "Default")
      (node (ref "IC1") (pin "15") (pinfunction "6Q_15") (pintype "tri_state"))
      (node (ref "IC11") (pin "15") (pinfunction "6Q_15") (pintype "tri_state"))
      (node (ref "IC3") (pin "15") (pinfunction "6Q_15") (pintype "tri_state"))
      (node (ref "IC5") (pin "15") (pinfunction "6Q_15") (pintype "tri_state"))
      (node (ref "JP5") (pin "12") (pinfunction "12_12") (pintype "passive"))
    )
    (net (code "66") (name "LBUS6") (class "Default")
      (node (ref "IC1") (pin "16") (pinfunction "7Q_16") (pintype "tri_state"))
      (node (ref "IC11") (pin "16") (pinfunction "7Q_16") (pintype "tri_state"))
      (node (ref "IC3") (pin "16") (pinfunction "7Q_16") (pintype "tri_state"))
      (node (ref "IC5") (pin "16") (pinfunction "7Q_16") (pintype "tri_state"))
      (node (ref "JP5") (pin "9") (pinfunction "9_9") (pintype "passive"))
    )
    (net (code "67") (name "LBUS7") (class "Default")
      (node (ref "IC1") (pin "19") (pinfunction "8Q_19") (pintype "tri_state"))
      (node (ref "IC11") (pin "19") (pinfunction "8Q_19") (pintype "tri_state"))
      (node (ref "IC3") (pin "19") (pinfunction "8Q_19") (pintype "tri_state"))
      (node (ref "IC5") (pin "19") (pinfunction "8Q_19") (pintype "tri_state"))
      (node (ref "JP5") (pin "10") (pinfunction "10_10") (pintype "passive"))
    )
    (net (code "68") (name "LBUS8") (class "Default")
      (node (ref "IC13") (pin "2") (pinfunction "1Q_2") (pintype "tri_state"))
      (node (ref "IC2") (pin "2") (pinfunction "1Q_2") (pintype "tri_state"))
      (node (ref "IC4") (pin "2") (pinfunction "1Q_2") (pintype "tri_state"))
      (node (ref "IC6") (pin "2") (pinfunction "1Q_2") (pintype "tri_state"))
      (node (ref "JP5") (pin "7") (pinfunction "7_7") (pintype "passive"))
    )
    (net (code "69") (name "LBUS9") (class "Default")
      (node (ref "IC13") (pin "5") (pinfunction "2Q_5") (pintype "tri_state"))
      (node (ref "IC2") (pin "5") (pinfunction "2Q_5") (pintype "tri_state"))
      (node (ref "IC4") (pin "5") (pinfunction "2Q_5") (pintype "tri_state"))
      (node (ref "IC6") (pin "5") (pinfunction "2Q_5") (pintype "tri_state"))
      (node (ref "JP5") (pin "8") (pinfunction "8_8") (pintype "passive"))
    )
    (net (code "70") (name "LBUS10") (class "Default")
      (node (ref "IC13") (pin "6") (pinfunction "3Q_6") (pintype "tri_state"))
      (node (ref "IC2") (pin "6") (pinfunction "3Q_6") (pintype "tri_state"))
      (node (ref "IC4") (pin "6") (pinfunction "3Q_6") (pintype "tri_state"))
      (node (ref "IC6") (pin "6") (pinfunction "3Q_6") (pintype "tri_state"))
      (node (ref "JP5") (pin "5") (pinfunction "5_5") (pintype "passive"))
    )
    (net (code "71") (name "LBUS11") (class "Default")
      (node (ref "IC13") (pin "9") (pinfunction "4Q_9") (pintype "tri_state"))
      (node (ref "IC2") (pin "9") (pinfunction "4Q_9") (pintype "tri_state"))
      (node (ref "IC4") (pin "9") (pinfunction "4Q_9") (pintype "tri_state"))
      (node (ref "IC6") (pin "9") (pinfunction "4Q_9") (pintype "tri_state"))
      (node (ref "JP5") (pin "6") (pinfunction "6_6") (pintype "passive"))
    )
    (net (code "72") (name "LBUS12") (class "Default")
      (node (ref "IC13") (pin "12") (pinfunction "5Q_12") (pintype "tri_state"))
      (node (ref "IC2") (pin "12") (pinfunction "5Q_12") (pintype "tri_state"))
      (node (ref "IC4") (pin "12") (pinfunction "5Q_12") (pintype "tri_state"))
      (node (ref "IC6") (pin "12") (pinfunction "5Q_12") (pintype "tri_state"))
      (node (ref "JP5") (pin "3") (pinfunction "3_3") (pintype "passive"))
    )
    (net (code "73") (name "LBUS13") (class "Default")
      (node (ref "IC13") (pin "15") (pinfunction "6Q_15") (pintype "tri_state"))
      (node (ref "IC2") (pin "15") (pinfunction "6Q_15") (pintype "tri_state"))
      (node (ref "IC4") (pin "15") (pinfunction "6Q_15") (pintype "tri_state"))
      (node (ref "IC6") (pin "15") (pinfunction "6Q_15") (pintype "tri_state"))
      (node (ref "JP5") (pin "4") (pinfunction "4_4") (pintype "passive"))
    )
    (net (code "74") (name "LBUS14") (class "Default")
      (node (ref "IC13") (pin "16") (pinfunction "7Q_16") (pintype "tri_state"))
      (node (ref "IC2") (pin "16") (pinfunction "7Q_16") (pintype "tri_state"))
      (node (ref "IC4") (pin "16") (pinfunction "7Q_16") (pintype "tri_state"))
      (node (ref "IC6") (pin "16") (pinfunction "7Q_16") (pintype "tri_state"))
      (node (ref "JP5") (pin "1") (pinfunction "1_1") (pintype "passive"))
    )
    (net (code "75") (name "LBUS15") (class "Default")
      (node (ref "IC13") (pin "19") (pinfunction "8Q_19") (pintype "tri_state"))
      (node (ref "IC2") (pin "19") (pinfunction "8Q_19") (pintype "tri_state"))
      (node (ref "IC4") (pin "19") (pinfunction "8Q_19") (pintype "tri_state"))
      (node (ref "IC6") (pin "19") (pinfunction "8Q_19") (pintype "tri_state"))
      (node (ref "JP5") (pin "2") (pinfunction "2_2") (pintype "passive"))
    )
    (net (code "76") (name "LOAD_FLAGS0") (class "Default")
      (node (ref "JP9") (pin "24") (pinfunction "24_24") (pintype "passive"))
    )
    (net (code "77") (name "LOAD_FLAGS1") (class "Default")
      (node (ref "JP9") (pin "26") (pinfunction "26_26") (pintype "passive"))
    )
    (net (code "78") (name "MDRLDINHBT") (class "Default")
      (node (ref "IC22") (pin "2") (pinfunction "I1_2") (pintype "input"))
      (node (ref "IC22") (pin "5") (pinfunction "I1_5") (pintype "input"))
      (node (ref "JP9") (pin "43") (pinfunction "43_43") (pintype "passive"))
    )
    (net (code "79") (name "MEMSEG") (class "Default")
      (node (ref "JP10") (pin "14") (pinfunction "14_14") (pintype "passive"))
    )
    (net (code "80") (name "Net-(IC1A-CLK)") (class "Default")
      (node (ref "IC1") (pin "11") (pinfunction "CLK_11") (pintype "input"))
      (node (ref "IC21") (pin "8") (pinfunction "O_8") (pintype "output"))
    )
    (net (code "81") (name "Net-(IC11A-CLK)") (class "Default")
      (node (ref "IC11") (pin "11") (pinfunction "CLK_11") (pintype "input"))
      (node (ref "IC12") (pin "11") (pinfunction "CLK_11") (pintype "input"))
      (node (ref "IC22") (pin "3") (pinfunction "O_3") (pintype "output"))
    )
    (net (code "82") (name "Net-(IC13A-CLK)") (class "Default")
      (node (ref "IC13") (pin "11") (pinfunction "CLK_11") (pintype "input"))
      (node (ref "IC14") (pin "11") (pinfunction "CLK_11") (pintype "input"))
      (node (ref "IC22") (pin "6") (pinfunction "O_6") (pintype "output"))
    )
    (net (code "83") (name "Net-(IC21A-O)") (class "Default")
      (node (ref "IC21") (pin "3") (pinfunction "O_3") (pintype "output"))
      (node (ref "IC22") (pin "1") (pinfunction "I0_1") (pintype "input"))
    )
    (net (code "84") (name "Net-(IC21B-O)") (class "Default")
      (node (ref "IC21") (pin "6") (pinfunction "O_6") (pintype "output"))
      (node (ref "IC22") (pin "4") (pinfunction "I0_4") (pintype "input"))
    )
    (net (code "85") (name "Net-(IC21D-O)") (class "Default")
      (node (ref "IC2") (pin "11") (pinfunction "CLK_11") (pintype "input"))
      (node (ref "IC21") (pin "11") (pinfunction "O_11") (pintype "output"))
    )
    (net (code "86") (name "PROT") (class "Default")
      (node (ref "JP10") (pin "21") (pinfunction "21_21") (pintype "passive"))
    )
    (net (code "87") (name "RBUS0") (class "Default")
      (node (ref "IC12") (pin "2") (pinfunction "1Q_2") (pintype "tri_state"))
      (node (ref "JP4") (pin "1") (pinfunction "1_1") (pintype "passive"))
    )
    (net (code "88") (name "RBUS1") (class "Default")
      (node (ref "IC12") (pin "5") (pinfunction "2Q_5") (pintype "tri_state"))
      (node (ref "JP4") (pin "2") (pinfunction "2_2") (pintype "passive"))
    )
    (net (code "89") (name "RBUS2") (class "Default")
      (node (ref "IC12") (pin "6") (pinfunction "3Q_6") (pintype "tri_state"))
      (node (ref "JP4") (pin "3") (pinfunction "3_3") (pintype "passive"))
    )
    (net (code "90") (name "RBUS3") (class "Default")
      (node (ref "IC12") (pin "9") (pinfunction "4Q_9") (pintype "tri_state"))
      (node (ref "JP4") (pin "4") (pinfunction "4_4") (pintype "passive"))
    )
    (net (code "91") (name "RBUS4") (class "Default")
      (node (ref "IC12") (pin "12") (pinfunction "5Q_12") (pintype "tri_state"))
      (node (ref "JP4") (pin "5") (pinfunction "5_5") (pintype "passive"))
    )
    (net (code "92") (name "RBUS5") (class "Default")
      (node (ref "IC12") (pin "15") (pinfunction "6Q_15") (pintype "tri_state"))
      (node (ref "JP4") (pin "6") (pinfunction "6_6") (pintype "passive"))
    )
    (net (code "93") (name "RBUS6") (class "Default")
      (node (ref "IC12") (pin "16") (pinfunction "7Q_16") (pintype "tri_state"))
      (node (ref "JP4") (pin "7") (pinfunction "7_7") (pintype "passive"))
    )
    (net (code "94") (name "RBUS7") (class "Default")
      (node (ref "IC12") (pin "19") (pinfunction "8Q_19") (pintype "tri_state"))
      (node (ref "JP4") (pin "8") (pinfunction "8_8") (pintype "passive"))
    )
    (net (code "95") (name "RBUS8") (class "Default")
      (node (ref "IC14") (pin "2") (pinfunction "1Q_2") (pintype "tri_state"))
      (node (ref "JP4") (pin "9") (pinfunction "9_9") (pintype "passive"))
    )
    (net (code "96") (name "RBUS9") (class "Default")
      (node (ref "IC14") (pin "5") (pinfunction "2Q_5") (pintype "tri_state"))
      (node (ref "JP4") (pin "10") (pinfunction "10_10") (pintype "passive"))
    )
    (net (code "97") (name "RBUS10") (class "Default")
      (node (ref "IC14") (pin "6") (pinfunction "3Q_6") (pintype "tri_state"))
      (node (ref "JP4") (pin "11") (pinfunction "11_11") (pintype "passive"))
    )
    (net (code "98") (name "RBUS11") (class "Default")
      (node (ref "IC14") (pin "9") (pinfunction "4Q_9") (pintype "tri_state"))
      (node (ref "JP4") (pin "12") (pinfunction "12_12") (pintype "passive"))
    )
    (net (code "99") (name "RBUS12") (class "Default")
      (node (ref "IC14") (pin "12") (pinfunction "5Q_12") (pintype "tri_state"))
      (node (ref "JP4") (pin "13") (pinfunction "13_13") (pintype "passive"))
    )
    (net (code "100") (name "RBUS13") (class "Default")
      (node (ref "IC14") (pin "15") (pinfunction "6Q_15") (pintype "tri_state"))
      (node (ref "JP4") (pin "14") (pinfunction "14_14") (pintype "passive"))
    )
    (net (code "101") (name "RBUS14") (class "Default")
      (node (ref "IC14") (pin "16") (pinfunction "7Q_16") (pintype "tri_state"))
      (node (ref "JP4") (pin "15") (pinfunction "15_15") (pintype "passive"))
    )
    (net (code "102") (name "RBUS15") (class "Default")
      (node (ref "IC14") (pin "19") (pinfunction "8Q_19") (pintype "tri_state"))
      (node (ref "JP4") (pin "16") (pinfunction "16_16") (pintype "passive"))
    )
    (net (code "103") (name "RST") (class "Default")
      (node (ref "JP10") (pin "9") (pinfunction "9_9") (pintype "passive"))
    )
    (net (code "104") (name "SP_DIR") (class "Default")
      (node (ref "JP10") (pin "20") (pinfunction "20_20") (pintype "passive"))
    )
    (net (code "105") (name "unconnected-(IC22C-O-Pad8)") (class "Default")
      (node (ref "IC22") (pin "8") (pinfunction "O_8") (pintype "output"))
    )
    (net (code "106") (name "unconnected-(IC22D-O-Pad11)") (class "Default")
      (node (ref "IC22") (pin "11") (pinfunction "O_11") (pintype "output"))
    )
    (net (code "107") (name "unconnected-(JP9-Pad15)") (class "Default")
      (node (ref "JP9") (pin "15") (pinfunction "15_15") (pintype "passive"))
    )
    (net (code "108") (name "unconnected-(JP9-Pad28)") (class "Default")
      (node (ref "JP9") (pin "28") (pinfunction "28_28") (pintype "passive"))
    )
    (net (code "109") (name "unconnected-(JP9-Pad30)") (class "Default")
      (node (ref "JP9") (pin "30") (pinfunction "30_30") (pintype "passive"))
    )
    (net (code "110") (name "unconnected-(JP9-Pad37)") (class "Default")
      (node (ref "JP9") (pin "37") (pinfunction "37_37") (pintype "passive"))
    )
    (net (code "111") (name "{slash}ALUCARRYIN") (class "Default")
      (node (ref "JP9") (pin "2") (pinfunction "2_2") (pintype "passive"))
    )
    (net (code "112") (name "{slash}ALUHI2MEM") (class "Default")
      (node (ref "JP10") (pin "25") (pinfunction "25_25") (pintype "passive"))
    )
    (net (code "113") (name "{slash}ALULO2MEM") (class "Default")
      (node (ref "JP10") (pin "29") (pinfunction "29_29") (pintype "passive"))
    )
    (net (code "114") (name "{slash}ALUSHR") (class "Default")
      (node (ref "JP9") (pin "1") (pinfunction "1_1") (pintype "passive"))
    )
    (net (code "115") (name "{slash}BUSIFCEN") (class "Default")
      (node (ref "JP10") (pin "5") (pinfunction "5_5") (pintype "passive"))
    )
    (net (code "116") (name "{slash}CARRY1") (class "Default")
      (node (ref "JP9") (pin "29") (pinfunction "29_29") (pintype "passive"))
    )
    (net (code "117") (name "{slash}CARRY3") (class "Default")
      (node (ref "JP9") (pin "31") (pinfunction "31_31") (pintype "passive"))
    )
    (net (code "118") (name "{slash}CNTSP") (class "Default")
      (node (ref "JP10") (pin "3") (pinfunction "3_3") (pintype "passive"))
    )
    (net (code "119") (name "{slash}ENA") (class "Default")
      (node (ref "IC1") (pin "1") (pinfunction "OC_1") (pintype "input"))
      (node (ref "IC2") (pin "1") (pinfunction "OC_1") (pintype "input"))
      (node (ref "JP9") (pin "33") (pinfunction "33_33") (pintype "passive"))
    )
    (net (code "120") (name "{slash}ENABUS") (class "Default")
      (node (ref "JP10") (pin "22") (pinfunction "22_22") (pintype "passive"))
    )
    (net (code "121") (name "{slash}ENALU") (class "Default")
      (node (ref "JP9") (pin "39") (pinfunction "39_39") (pintype "passive"))
    )
    (net (code "122") (name "{slash}ENDP") (class "Default")
      (node (ref "IC10") (pin "1") (pinfunction "OC_1") (pintype "input"))
      (node (ref "IC9") (pin "1") (pinfunction "OC_1") (pintype "input"))
      (node (ref "JP9") (pin "44") (pinfunction "44_44") (pintype "passive"))
    )
    (net (code "123") (name "{slash}ENIPTR") (class "Default")
      (node (ref "JP9") (pin "38") (pinfunction "38_38") (pintype "passive"))
    )
    (net (code "124") (name "{slash}ENLMDR") (class "Default")
      (node (ref "IC11") (pin "1") (pinfunction "OC_1") (pintype "input"))
      (node (ref "IC13") (pin "1") (pinfunction "OC_1") (pintype "input"))
      (node (ref "JP9") (pin "34") (pinfunction "34_34") (pintype "passive"))
    )
    (net (code "125") (name "{slash}ENMAR") (class "Default")
      (node (ref "JP9") (pin "48") (pinfunction "48_48") (pintype "passive"))
    )
    (net (code "126") (name "{slash}ENMEM") (class "Default")
      (node (ref "JP10") (pin "16") (pinfunction "16_16") (pintype "passive"))
    )
    (net (code "127") (name "{slash}ENMSW") (class "Default")
      (node (ref "JP9") (pin "40") (pinfunction "40_40") (pintype "passive"))
    )
    (net (code "128") (name "{slash}ENPC") (class "Default")
      (node (ref "JP9") (pin "42") (pinfunction "42_42") (pintype "passive"))
    )
    (net (code "129") (name "{slash}ENRMDR") (class "Default")
      (node (ref "IC12") (pin "1") (pinfunction "OC_1") (pintype "input"))
      (node (ref "IC14") (pin "1") (pinfunction "OC_1") (pintype "input"))
      (node (ref "JP9") (pin "41") (pinfunction "41_41") (pintype "passive"))
    )
    (net (code "130") (name "{slash}ENSP") (class "Default")
      (node (ref "JP9") (pin "46") (pinfunction "46_46") (pintype "passive"))
    )
    (net (code "131") (name "{slash}ENX") (class "Default")
      (node (ref "IC3") (pin "1") (pinfunction "OC_1") (pintype "input"))
      (node (ref "IC4") (pin "1") (pinfunction "OC_1") (pintype "input"))
      (node (ref "JP9") (pin "36") (pinfunction "36_36") (pintype "passive"))
    )
    (net (code "132") (name "{slash}ENY") (class "Default")
      (node (ref "IC5") (pin "1") (pinfunction "OC_1") (pintype "input"))
      (node (ref "IC6") (pin "1") (pinfunction "OC_1") (pintype "input"))
      (node (ref "JP9") (pin "35") (pinfunction "35_35") (pintype "passive"))
    )
    (net (code "133") (name "{slash}FI") (class "Default")
      (node (ref "JP10") (pin "32") (pinfunction "32_32") (pintype "passive"))
    )
    (net (code "134") (name "{slash}FP") (class "Default")
      (node (ref "JP10") (pin "34") (pinfunction "34_34") (pintype "passive"))
    )
    (net (code "135") (name "{slash}FS") (class "Default")
      (node (ref "JP10") (pin "30") (pinfunction "30_30") (pintype "passive"))
    )
    (net (code "136") (name "{slash}INCPC") (class "Default")
      (node (ref "JP10") (pin "1") (pinfunction "1_1") (pintype "passive"))
    )
    (net (code "137") (name "{slash}INC_MAR") (class "Default")
      (node (ref "JP9") (pin "32") (pinfunction "32_32") (pintype "passive"))
    )
    (net (code "138") (name "{slash}IO") (class "Default")
      (node (ref "JP10") (pin "35") (pinfunction "35_35") (pintype "passive"))
    )
    (net (code "139") (name "{slash}LATCHFLAGS") (class "Default")
      (node (ref "JP10") (pin "12") (pinfunction "12_12") (pintype "passive"))
    )
    (net (code "140") (name "{slash}LATCH_I") (class "Default")
      (node (ref "JP9") (pin "47") (pinfunction "47_47") (pintype "passive"))
    )
    (net (code "141") (name "{slash}LATCH_S") (class "Default")
      (node (ref "JP9") (pin "45") (pinfunction "45_45") (pintype "passive"))
    )
    (net (code "142") (name "{slash}LDA") (class "Default")
      (node (ref "IC21") (pin "10") (pinfunction "I1_10") (pintype "input"))
      (node (ref "IC21") (pin "13") (pinfunction "I1_13") (pintype "input"))
      (node (ref "JP9") (pin "14") (pinfunction "14_14") (pintype "passive"))
    )
    (net (code "143") (name "{slash}LDAHI") (class "Default")
      (node (ref "IC21") (pin "12") (pinfunction "I0_12") (pintype "input"))
      (node (ref "JP9") (pin "11") (pinfunction "11_11") (pintype "passive"))
    )
    (net (code "144") (name "{slash}LDALO") (class "Default")
      (node (ref "IC21") (pin "9") (pinfunction "I0_9") (pintype "input"))
      (node (ref "JP9") (pin "12") (pinfunction "12_12") (pintype "passive"))
    )
    (net (code "145") (name "{slash}LDDP") (class "Default")
      (node (ref "IC10") (pin "11") (pinfunction "CLK_11") (pintype "input"))
      (node (ref "IC9") (pin "11") (pinfunction "CLK_11") (pintype "input"))
      (node (ref "JP9") (pin "22") (pinfunction "22_22") (pintype "passive"))
    )
    (net (code "146") (name "{slash}LDMAR") (class "Default")
      (node (ref "JP9") (pin "23") (pinfunction "23_23") (pintype "passive"))
    )
    (net (code "147") (name "{slash}LDMARHI") (class "Default")
      (node (ref "JP9") (pin "17") (pinfunction "17_17") (pintype "passive"))
    )
    (net (code "148") (name "{slash}LDMARLO") (class "Default")
      (node (ref "JP9") (pin "18") (pinfunction "18_18") (pintype "passive"))
    )
    (net (code "149") (name "{slash}LDMDR") (class "Default")
      (node (ref "IC21") (pin "1") (pinfunction "I0_1") (pintype "input"))
      (node (ref "IC21") (pin "4") (pinfunction "I0_4") (pintype "input"))
      (node (ref "JP9") (pin "9") (pinfunction "9_9") (pintype "passive"))
    )
    (net (code "150") (name "{slash}LDMDRHI") (class "Default")
      (node (ref "IC21") (pin "5") (pinfunction "I1_5") (pintype "input"))
      (node (ref "JP9") (pin "10") (pinfunction "10_10") (pintype "passive"))
    )
    (net (code "151") (name "{slash}LDMDRLO") (class "Default")
      (node (ref "IC21") (pin "2") (pinfunction "I1_2") (pintype "input"))
      (node (ref "JP9") (pin "7") (pinfunction "7_7") (pintype "passive"))
    )
    (net (code "152") (name "{slash}LDMEM") (class "Default")
      (node (ref "JP10") (pin "15") (pinfunction "15_15") (pintype "passive"))
    )
    (net (code "153") (name "{slash}LDMSW") (class "Default")
      (node (ref "JP9") (pin "20") (pinfunction "20_20") (pintype "passive"))
    )
    (net (code "154") (name "{slash}LDPC") (class "Default")
      (node (ref "JP9") (pin "19") (pinfunction "19_19") (pintype "passive"))
    )
    (net (code "155") (name "{slash}LDSP") (class "Default")
      (node (ref "JP9") (pin "21") (pinfunction "21_21") (pintype "passive"))
    )
    (net (code "156") (name "{slash}LDX") (class "Default")
      (node (ref "IC3") (pin "11") (pinfunction "CLK_11") (pintype "input"))
      (node (ref "IC4") (pin "11") (pinfunction "CLK_11") (pintype "input"))
      (node (ref "JP9") (pin "13") (pinfunction "13_13") (pintype "passive"))
    )
    (net (code "157") (name "{slash}LDY") (class "Default")
      (node (ref "IC5") (pin "11") (pinfunction "CLK_11") (pintype "input"))
      (node (ref "IC6") (pin "11") (pinfunction "CLK_11") (pintype "input"))
      (node (ref "JP9") (pin "16") (pinfunction "16_16") (pintype "passive"))
    )
    (net (code "158") (name "{slash}LOAD_IR") (class "Default")
      (node (ref "JP10") (pin "26") (pinfunction "26_26") (pintype "passive"))
    )
    (net (code "159") (name "{slash}MEM2ALUHI") (class "Default")
      (node (ref "JP10") (pin "27") (pinfunction "27_27") (pintype "passive"))
    )
    (net (code "160") (name "{slash}MEM2ALULO") (class "Default")
      (node (ref "JP10") (pin "31") (pinfunction "31_31") (pintype "passive"))
    )
    (net (code "161") (name "{slash}MEMOP") (class "Default")
      (node (ref "JP10") (pin "11") (pinfunction "11_11") (pintype "passive"))
    )
    (net (code "162") (name "{slash}NP_FAULT") (class "Default")
      (node (ref "JP10") (pin "36") (pinfunction "36_36") (pintype "passive"))
    )
    (net (code "163") (name "{slash}RST") (class "Default")
      (node (ref "JP10") (pin "7") (pinfunction "7_7") (pintype "passive"))
    )
    (net (code "164") (name "{slash}WR_FAULT") (class "Default")
      (node (ref "JP10") (pin "33") (pinfunction "33_33") (pintype "passive"))
    )
  )
)
